# V3_0.net
KiCad netlist of a schematic drawn in Altium Designer
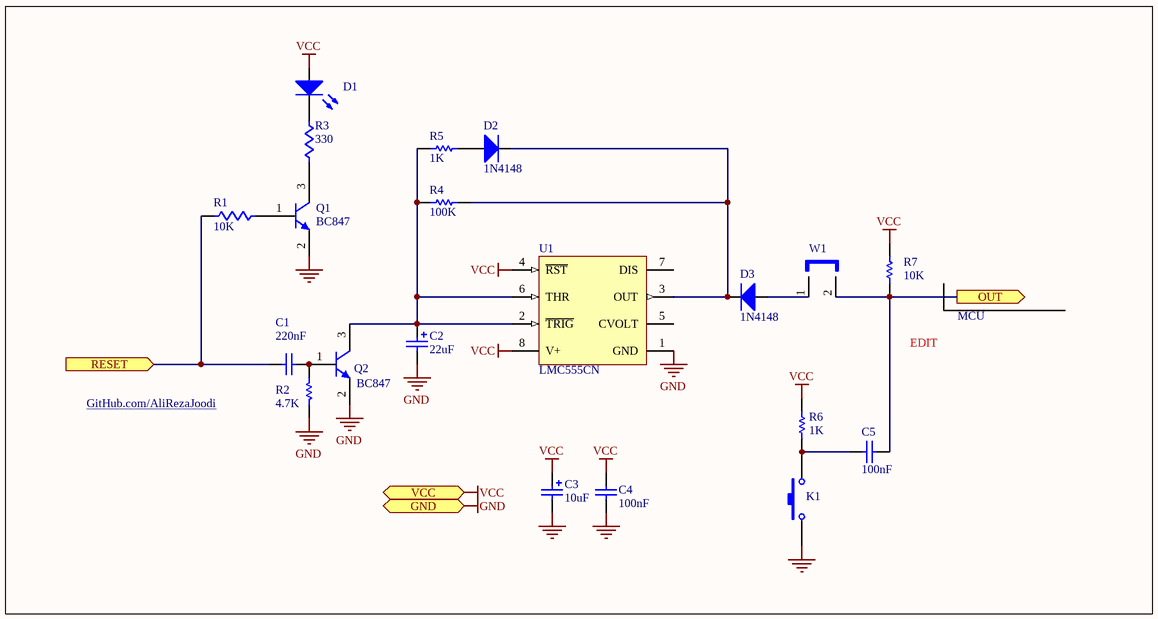
[diagram p0: V3.0.SchDoc]

(export (version "E")
  (design (tool "Eeschema 10.0.6"))
  (components
    (comp (ref "C1")
      (value "220nF")
      (footprint "RESC3216N")
      (description "Capacitor")
      (fields (field (name "Comment") "Cap") (field (name "PUBLISHER") "Altium Limited"))
      (libsource (lib "Miscellaneous Devices") (part "Cap"))
    )
    (comp (ref "C2")
      (value "22uF")
      (footprint "Cap_B")
      (description "Polarized Capacitor (Radial)")
      (fields
        (field (name "MANUFACTURER") "Generic Components")
        (field (name "Comment") "Capacitor")
        (field (name "PUBLISHER") "Altium Limited")
      )
      (libsource (lib "Miscellaneous Devices") (part "Cap Pol1"))
    )
    (comp (ref "C3")
      (value "10uF")
      (footprint "Cap_B")
      (description "Polarized Capacitor (Radial)")
      (fields
        (field (name "MANUFACTURER") "Generic Components")
        (field (name "Comment") "Capacitor")
        (field (name "PUBLISHER") "Altium Limited")
      )
      (libsource (lib "Miscellaneous Devices") (part "Cap Pol1"))
    )
    (comp (ref "C4")
      (value "100nF")
      (footprint "0805")
      (description "Capacitor")
      (fields
        (field (name "MANUFACTURER") "Generic Components")
        (field (name "Comment") "Cap")
        (field (name "PUBLISHER") "Altium Limited")
      )
      (libsource (lib "Miscellaneous Devices") (part "Cap"))
    )
    (comp (ref "C5")
      (value "100nF")
      (footprint "0805")
      (description "Capacitor")
      (fields
        (field (name "MANUFACTURER") "Generic Components")
        (field (name "Comment") "Cap")
        (field (name "PUBLISHER") "Altium Limited")
      )
      (libsource (lib "Miscellaneous Devices") (part "Cap"))
    )
    (comp (ref "D1")
      (value "LED")
      (footprint "0805_Diode")
      (description "Typical INFRARED GaAs LED")
      (fields (field (name "MANUFACTURER") "Generic Components") (field (name "PUBLISHER") "Altium Limited"))
      (libsource (lib "Miscellaneous Devices") (part "LED"))
    )
    (comp (ref "D2")
      (value "1N4148")
      (footprint "0805_Diode")
      (description "Default Diode")
      (fields
        (field (name "MANUFACTURER") "Generic Components")
        (field (name "Comment") "Diode")
        (field (name "PUBLISHER") "Altium Limited")
      )
      (libsource (lib "Miscellaneous Devices") (part "Diode"))
    )
    (comp (ref "D3")
      (value "1N4148")
      (footprint "0805_Diode")
      (description "Default Diode")
      (fields
        (field (name "MANUFACTURER") "Generic Components")
        (field (name "Comment") "Diode")
        (field (name "PUBLISHER") "Altium Limited")
      )
      (libsource (lib "Miscellaneous Devices") (part "Diode"))
    )
    (comp (ref "K1")
      (value "SW-PB")
      (footprint "SPST-2_2")
      (description "Switch")
      (fields (field (name "MANUFACTURER") "Generic Components") (field (name "PUBLISHER") "Altium Limited"))
      (libsource (lib "Miscellaneous Devices") (part "SW-PB"))
    )
    (comp (ref "Q1")
      (value "BC847")
      (footprint "SOT23-3N")
      (description "Silicon Bipolar Transistor")
      (fields (field (name "Comment") "NPN"))
      (libsource (lib "my Libraries") (part "BC847"))
    )
    (comp (ref "Q2")
      (value "BC847")
      (footprint "SOT23-3N")
      (description "Silicon Bipolar Transistor")
      (fields (field (name "Comment") "NPN"))
      (libsource (lib "my Libraries") (part "BC847"))
    )
    (comp (ref "R1")
      (value "10K")
      (footprint "0805")
      (description "Resistor")
      (fields
        (field (name "MANUFACTURER") "Generic Components")
        (field (name "Comment") "RES")
        (field (name "PUBLISHER") "Altium Limited")
      )
      (libsource (lib "") (part "Res1_1"))
    )
    (comp (ref "R2")
      (value "4.7K")
      (footprint "0805")
      (description "Resistor")
      (fields (field (name "Comment") "Res1") (field (name "PUBLISHER") "Altium Limited"))
      (libsource (lib "Miscellaneous Devices") (part "Res1"))
    )
    (comp (ref "R3")
      (value "330")
      (footprint "0805")
      (description "Resistor")
      (fields
        (field (name "MANUFACTURER") "Generic Components")
        (field (name "Comment") "RES")
        (field (name "PUBLISHER") "Altium Limited")
      )
      (libsource (lib "") (part "Res1_1"))
    )
    (comp (ref "R4")
      (value "100K")
      (footprint "0805")
      (description "Resistor")
      (fields (field (name "Comment") "Res1") (field (name "PUBLISHER") "Altium Limited"))
      (libsource (lib "Miscellaneous Devices") (part "Res1"))
    )
    (comp (ref "R5")
      (value "1K")
      (footprint "0805")
      (description "Resistor")
      (fields (field (name "Comment") "Res1") (field (name "PUBLISHER") "Altium Limited"))
      (libsource (lib "Miscellaneous Devices") (part "Res1"))
    )
    (comp (ref "R6")
      (value "1K")
      (footprint "0805")
      (description "Resistor")
      (fields (field (name "MANUFACTURER") "Generic Components") (field (name "PUBLISHER") "Altium Limited"))
      (libsource (lib "Miscellaneous Devices") (part "Res1"))
    )
    (comp (ref "R7")
      (value "10K")
      (footprint "0805")
      (description "Resistor")
      (fields
        (field (name "MANUFACTURER") "Generic Components")
        (field (name "Comment") "Res1")
        (field (name "PUBLISHER") "Altium Limited")
      )
      (libsource (lib "Miscellaneous Devices") (part "Res1"))
    )
    (comp (ref "U1")
      (value "LMC555CN")
      (footprint "SOP127P636-8N")
      (description "CMOS Timer, 8-pin MDIP")
      (fields
        (field (name "MANUFACTURER") "National Semiconductor")
        (field (name "PUBLISHER") "Altium Limited")
      )
      (libsource (lib "NSC Analog") (part "LMC555CN"))
    )
    (comp (ref "W1")
      (value "Jumper 2pin")
      (footprint "HDR1X2")
      (description "Jumper Wire")
      (fields (field (name "MANUFACTURER") "Generic Components") (field (name "PUBLISHER") "Altium Limited"))
      (libsource (lib "my Libraries") (part "Jumper 2pin"))
    )
  )
  (nets
    (net (code "1") (name "/OUT") (class "Default")
      (node (ref "C5") (pin "1") (pinfunction "1_1") (pintype "passive"))
      (node (ref "R7") (pin "2") (pinfunction "2_2") (pintype "passive"))
      (node (ref "W1") (pin "2") (pinfunction "2_2") (pintype "passive"))
    )
    (net (code "2") (name "/RESET") (class "Default")
      (node (ref "C1") (pin "1") (pinfunction "1_1") (pintype "passive"))
      (node (ref "R1") (pin "1") (pinfunction "1_1") (pintype "passive"))
    )
    (net (code "3") (name "GND") (class "Default")
      (node (ref "C2") (pin "2") (pinfunction "2_2") (pintype "passive"))
      (node (ref "C3") (pin "2") (pinfunction "2_2") (pintype "passive"))
      (node (ref "C4") (pin "1") (pinfunction "1_1") (pintype "passive"))
      (node (ref "K1") (pin "1") (pinfunction "1_1") (pintype "passive"))
      (node (ref "Q1") (pin "2") (pinfunction "E_2") (pintype "passive"))
      (node (ref "Q2") (pin "2") (pinfunction "E_2") (pintype "passive"))
      (node (ref "R2") (pin "2") (pinfunction "2_2") (pintype "passive"))
      (node (ref "U1") (pin "1") (pinfunction "GND_1") (pintype "power_in"))
    )
    (net (code "4") (name "Net-(C5-Pad2)") (class "Default")
      (node (ref "C5") (pin "2") (pinfunction "2_2") (pintype "passive"))
      (node (ref "K1") (pin "2") (pinfunction "2_2") (pintype "passive"))
      (node (ref "R6") (pin "2") (pinfunction "2_2") (pintype "passive"))
    )
    (net (code "5") (name "Net-(D1-K)") (class "Default")
      (node (ref "D1") (pin "2") (pinfunction "K_2") (pintype "passive"))
      (node (ref "R3") (pin "1") (pinfunction "1_1") (pintype "passive"))
    )
    (net (code "6") (name "Net-(D2-A)") (class "Default")
      (node (ref "D2") (pin "1") (pinfunction "A_1") (pintype "passive"))
      (node (ref "R5") (pin "2") (pinfunction "2_2") (pintype "passive"))
    )
    (net (code "7") (name "Net-(D2-K)") (class "Default")
      (node (ref "D2") (pin "2") (pinfunction "K_2") (pintype "passive"))
      (node (ref "D3") (pin "2") (pinfunction "K_2") (pintype "passive"))
      (node (ref "R4") (pin "2") (pinfunction "2_2") (pintype "passive"))
      (node (ref "U1") (pin "3") (pinfunction "OUT_3") (pintype "output"))
    )
    (net (code "8") (name "Net-(D3-A)") (class "Default")
      (node (ref "D3") (pin "1") (pinfunction "A_1") (pintype "passive"))
      (node (ref "W1") (pin "1") (pinfunction "1_1") (pintype "passive"))
    )
    (net (code "9") (name "Net-(Q1-B)") (class "Default")
      (node (ref "Q1") (pin "1") (pinfunction "B_1") (pintype "passive"))
      (node (ref "R1") (pin "2") (pinfunction "2_2") (pintype "passive"))
    )
    (net (code "10") (name "Net-(Q1-C)") (class "Default")
      (node (ref "Q1") (pin "3") (pinfunction "C_3") (pintype "passive"))
      (node (ref "R3") (pin "2") (pinfunction "2_2") (pintype "passive"))
    )
    (net (code "11") (name "Net-(Q2-B)") (class "Default")
      (node (ref "C1") (pin "2") (pinfunction "2_2") (pintype "passive"))
      (node (ref "Q2") (pin "1") (pinfunction "B_1") (pintype "passive"))
      (node (ref "R2") (pin "1") (pinfunction "1_1") (pintype "passive"))
    )
    (net (code "12") (name "Net-(Q2-C)") (class "Default")
      (node (ref "C2") (pin "1") (pinfunction "1_1") (pintype "passive"))
      (node (ref "Q2") (pin "3") (pinfunction "C_3") (pintype "passive"))
      (node (ref "R4") (pin "1") (pinfunction "1_1") (pintype "passive"))
      (node (ref "R5") (pin "1") (pinfunction "1_1") (pintype "passive"))
      (node (ref "U1") (pin "2") (pinfunction "~{TRIG}_2") (pintype "input"))
      (node (ref "U1") (pin "6") (pinfunction "THR_6") (pintype "input"))
    )
    (net (code "13") (name "VCC") (class "Default")
      (node (ref "C3") (pin "1") (pinfunction "1_1") (pintype "passive"))
      (node (ref "C4") (pin "2") (pinfunction "2_2") (pintype "passive"))
      (node (ref "D1") (pin "1") (pinfunction "A_1") (pintype "passive"))
      (node (ref "R6") (pin "1") (pinfunction "1_1") (pintype "passive"))
      (node (ref "R7") (pin "1") (pinfunction "1_1") (pintype "passive"))
      (node (ref "U1") (pin "4") (pinfunction "~{RST}_4") (pintype "input"))
      (node (ref "U1") (pin "8") (pinfunction "V+_8") (pintype "power_in"))
    )
    (net (code "14") (name "unconnected-(U1-CVOLT-Pad5)") (class "Default")
      (node (ref "U1") (pin "5") (pinfunction "CVOLT_5") (pintype "passive"))
    )
    (net (code "15") (name "unconnected-(U1-DIS-Pad7)") (class "Default")
      (node (ref "U1") (pin "7") (pinfunction "DIS_7") (pintype "open_collector"))
    )
  )
)
